# stm32hw05.net
KiCad netlist of a schematic drawn in EAGLE
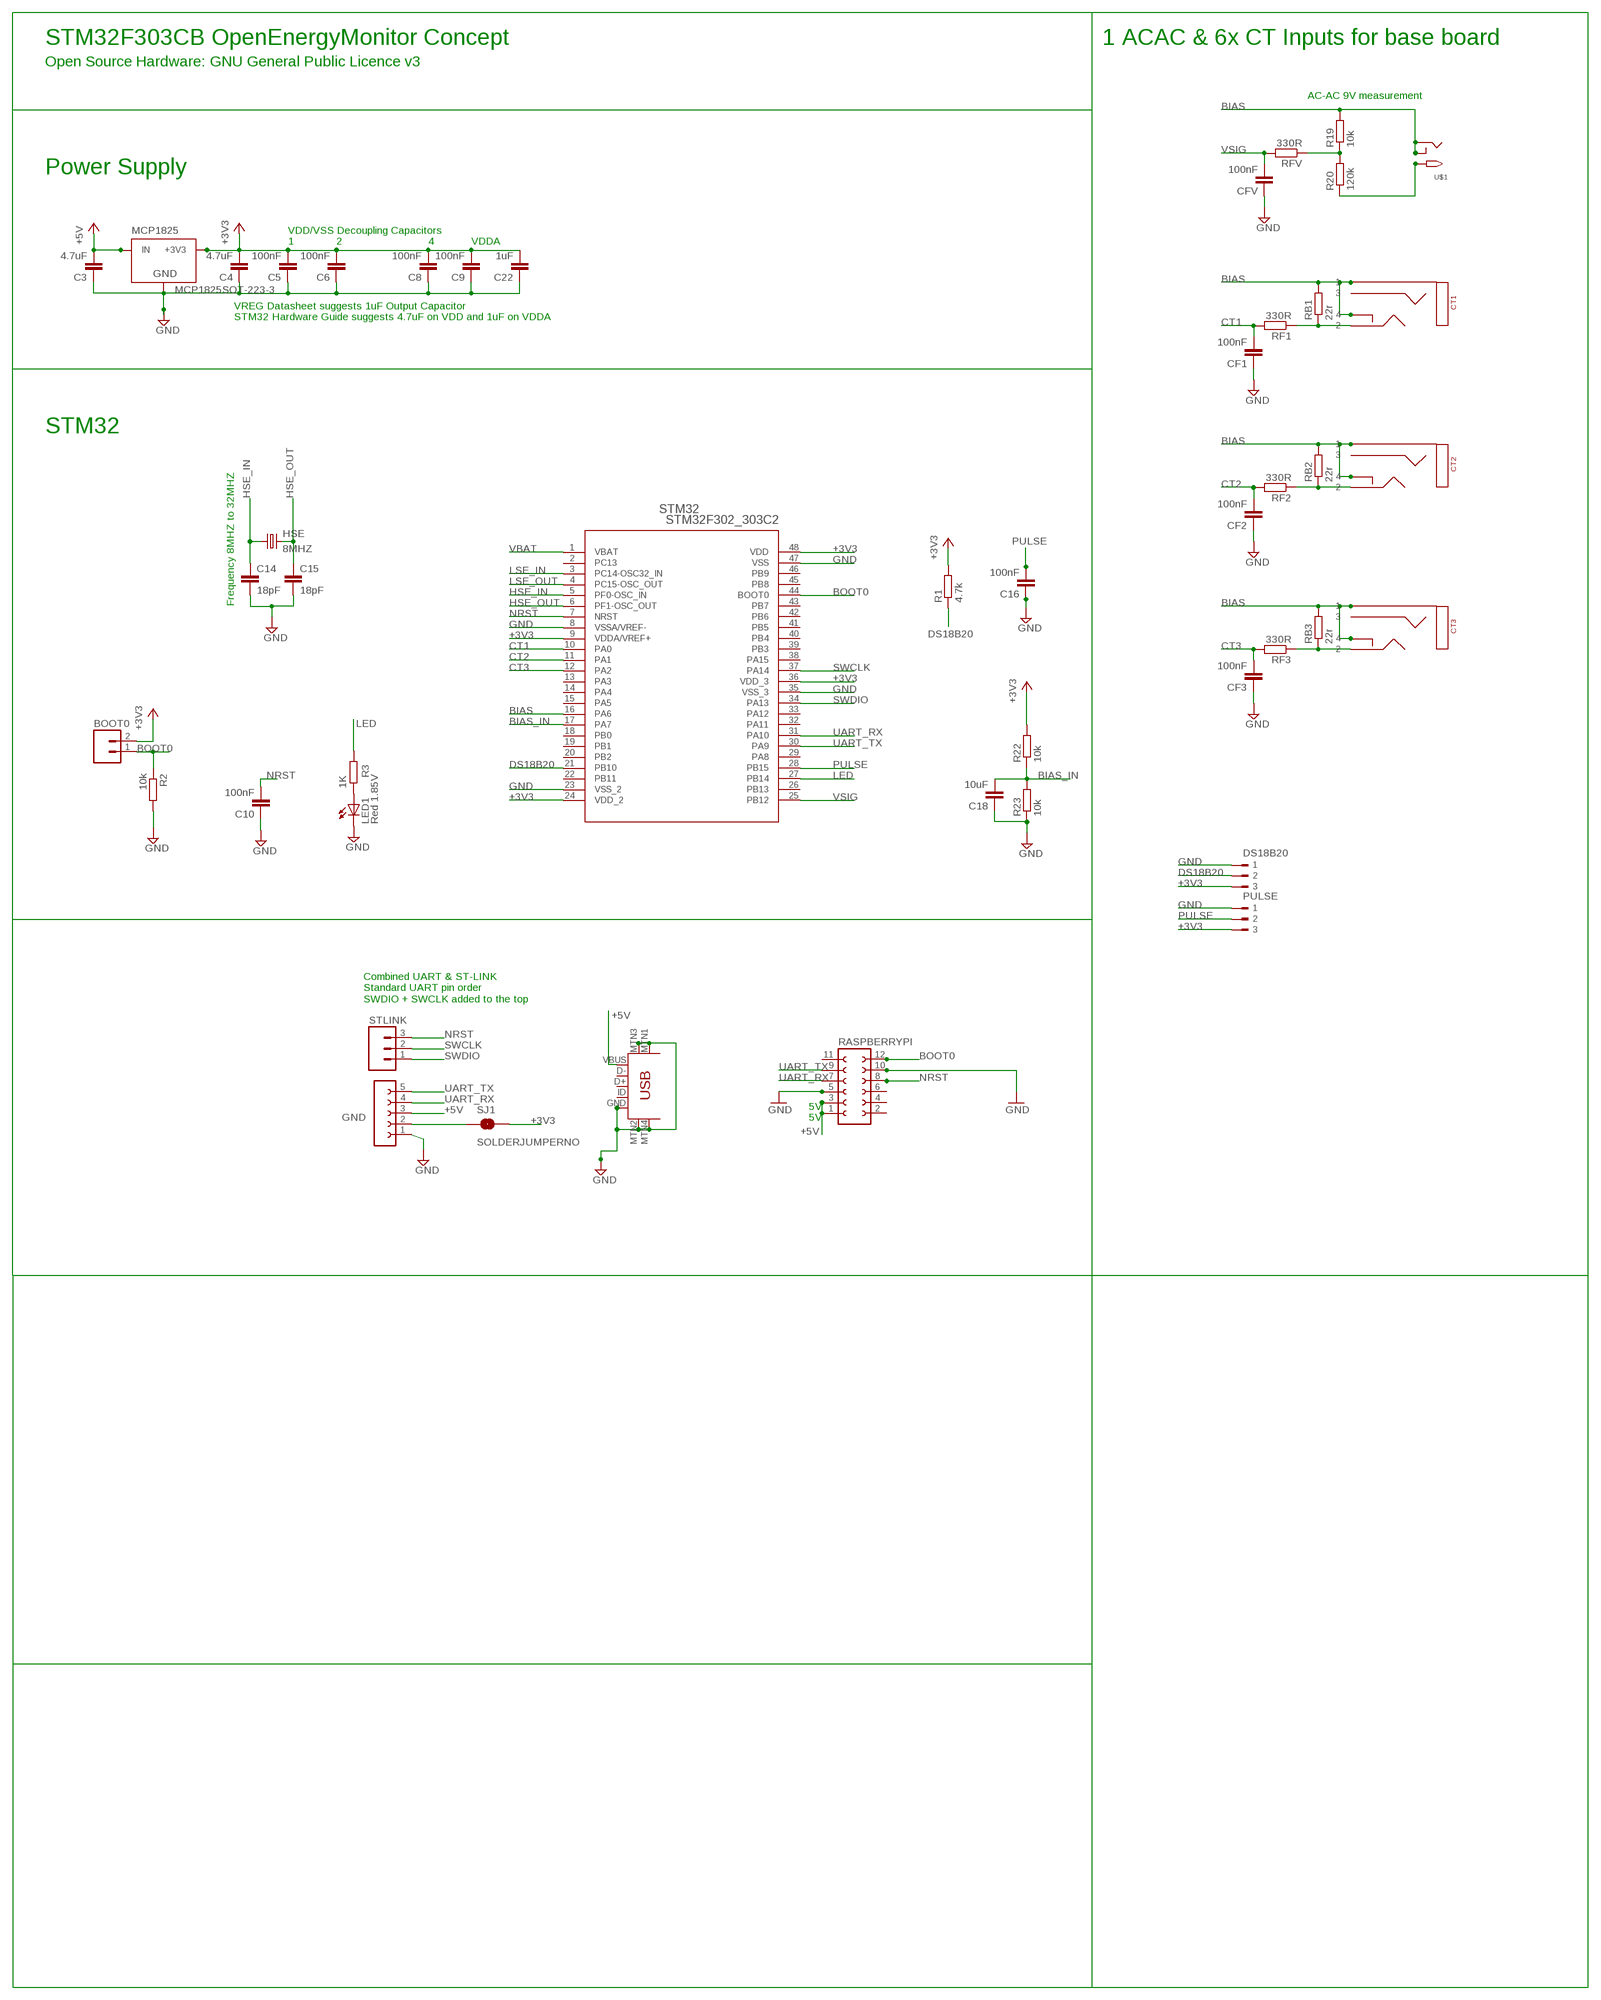
[diagram p0: schematic, sheet 1]

(export (version "E")
  (design (tool "Eeschema 10.0.6"))
  (components
    (comp (ref "BOOT0")
      (value "M02PTH")
      (footprint "eagle-import:1X02")
      (libsource (lib "eagle-import") (part "M02PTH"))
    )
    (comp (ref "C3")
      (value "4.7uF")
      (footprint "eagle-import:C0603")
      (libsource (lib "eagle-import") (part "C-EUC0603"))
    )
    (comp (ref "C4")
      (value "4.7uF")
      (footprint "eagle-import:C0603")
      (libsource (lib "eagle-import") (part "C-EUC0603"))
    )
    (comp (ref "C5")
      (value "100nF")
      (footprint "eagle-import:C0603")
      (libsource (lib "eagle-import") (part "C-EUC0603"))
    )
    (comp (ref "C6")
      (value "100nF")
      (footprint "eagle-import:C0603")
      (libsource (lib "eagle-import") (part "C-EUC0603"))
    )
    (comp (ref "C8")
      (value "100nF")
      (footprint "eagle-import:C0603")
      (libsource (lib "eagle-import") (part "C-EUC0603"))
    )
    (comp (ref "C9")
      (value "100nF")
      (footprint "eagle-import:C0603")
      (libsource (lib "eagle-import") (part "C-EUC0603"))
    )
    (comp (ref "C10")
      (value "100nF")
      (footprint "eagle-import:C0603")
      (libsource (lib "eagle-import") (part "C-EUC0603"))
    )
    (comp (ref "C14")
      (value "18pF")
      (footprint "eagle-import:C0603")
      (libsource (lib "eagle-import") (part "C-EUC0603"))
    )
    (comp (ref "C15")
      (value "18pF")
      (footprint "eagle-import:C0603")
      (libsource (lib "eagle-import") (part "C-EUC0603"))
    )
    (comp (ref "C16")
      (value "100nF")
      (footprint "eagle-import:C0603")
      (libsource (lib "eagle-import") (part "C-EUC0603"))
    )
    (comp (ref "C18")
      (value "10uF")
      (footprint "eagle-import:C0603")
      (libsource (lib "eagle-import") (part "C-EUC0603"))
    )
    (comp (ref "C22")
      (value "1uF")
      (footprint "eagle-import:C0603")
      (libsource (lib "eagle-import") (part "C-EUC0603"))
    )
    (comp (ref "CF1")
      (value "100nF")
      (footprint "eagle-import:C0603")
      (libsource (lib "eagle-import") (part "C-EUC0603"))
    )
    (comp (ref "CF2")
      (value "100nF")
      (footprint "eagle-import:C0603")
      (libsource (lib "eagle-import") (part "C-EUC0603"))
    )
    (comp (ref "CF3")
      (value "100nF")
      (footprint "eagle-import:C0603")
      (libsource (lib "eagle-import") (part "C-EUC0603"))
    )
    (comp (ref "CFV")
      (value "100nF")
      (footprint "eagle-import:C0603")
      (libsource (lib "eagle-import") (part "C-EUC0603"))
    )
    (comp (ref "CT1")
      (value "STEREO_SMD")
      (footprint "eagle-import:STEREO_SMT")
      (libsource (lib "eagle-import") (part "STEREO_SMD"))
    )
    (comp (ref "CT2")
      (value "STEREO_SMD")
      (footprint "eagle-import:STEREO_SMT")
      (libsource (lib "eagle-import") (part "STEREO_SMD"))
    )
    (comp (ref "CT3")
      (value "STEREO_SMD")
      (footprint "eagle-import:STEREO_SMT")
      (libsource (lib "eagle-import") (part "STEREO_SMD"))
    )
    (comp (ref "DS18B20")
      (value "180-3")
      (footprint "eagle-import:180-3")
      (libsource (lib "eagle-import") (part "180-3"))
    )
    (comp (ref "GND")
      (value "UART")
      (footprint "eagle-import:FE05-1")
      (libsource (lib "eagle-import") (part "FE05-1"))
    )
    (comp (ref "HSE")
      (value "8MHZ")
      (footprint "eagle-import:CTS406")
      (libsource (lib "eagle-import") (part "CRYSTALCTS406"))
    )
    (comp (ref "LED1")
      (value "Red 1.85V")
      (footprint "eagle-import:CHIP-LED0805")
      (libsource (lib "eagle-import") (part "LEDCHIP-LED0805"))
    )
    (comp (ref "MCP1825")
      (value "MCP1825SOT-223-3")
      (footprint "eagle-import:SOT-223")
      (libsource (lib "eagle-import") (part "MCP1825SOT-223-3"))
    )
    (comp (ref "PULSE")
      (value "180-3")
      (footprint "eagle-import:180-3")
      (libsource (lib "eagle-import") (part "180-3"))
    )
    (comp (ref "R1")
      (value "4.7k")
      (footprint "eagle-import:R0603")
      (libsource (lib "eagle-import") (part "resistor_R-EU_R0603"))
    )
    (comp (ref "R2")
      (value "10k")
      (footprint "eagle-import:R0603")
      (libsource (lib "eagle-import") (part "resistor_R-EU_R0603"))
    )
    (comp (ref "R3")
      (value "1K")
      (footprint "eagle-import:R0603")
      (libsource (lib "eagle-import") (part "R-EU_R0603"))
    )
    (comp (ref "R19")
      (value "10k")
      (footprint "eagle-import:R0603")
      (libsource (lib "eagle-import") (part "resistor_R-EU_R0603"))
    )
    (comp (ref "R20")
      (value "120k")
      (footprint "eagle-import:R0603")
      (libsource (lib "eagle-import") (part "resistor_R-EU_R0603"))
    )
    (comp (ref "R22")
      (value "10k")
      (footprint "eagle-import:R0603")
      (libsource (lib "eagle-import") (part "resistor_R-EU_R0603"))
    )
    (comp (ref "R23")
      (value "10k")
      (footprint "eagle-import:R0603")
      (libsource (lib "eagle-import") (part "resistor_R-EU_R0603"))
    )
    (comp (ref "RASPBERRYPI")
      (value "FE06-2")
      (footprint "eagle-import:FE06-2")
      (libsource (lib "eagle-import") (part "FE06-2"))
    )
    (comp (ref "RB1")
      (value "22r")
      (footprint "eagle-import:R0603")
      (libsource (lib "eagle-import") (part "resistor_R-EU_R0603"))
    )
    (comp (ref "RB2")
      (value "22r")
      (footprint "eagle-import:R0603")
      (libsource (lib "eagle-import") (part "resistor_R-EU_R0603"))
    )
    (comp (ref "RB3")
      (value "22r")
      (footprint "eagle-import:R0603")
      (libsource (lib "eagle-import") (part "resistor_R-EU_R0603"))
    )
    (comp (ref "RF1")
      (value "330R")
      (footprint "eagle-import:R0603")
      (libsource (lib "eagle-import") (part "resistor_R-EU_R0603"))
    )
    (comp (ref "RF2")
      (value "330R")
      (footprint "eagle-import:R0603")
      (libsource (lib "eagle-import") (part "resistor_R-EU_R0603"))
    )
    (comp (ref "RF3")
      (value "330R")
      (footprint "eagle-import:R0603")
      (libsource (lib "eagle-import") (part "resistor_R-EU_R0603"))
    )
    (comp (ref "RFV")
      (value "330R")
      (footprint "eagle-import:R0603")
      (libsource (lib "eagle-import") (part "resistor_R-EU_R0603"))
    )
    (comp (ref "SJ1")
      (value "SOLDERJUMPERNO")
      (footprint "eagle-import:SJ_2S-NO")
      (libsource (lib "eagle-import") (part "SOLDERJUMPERNO"))
    )
    (comp (ref "STLINK")
      (value "M03PTH")
      (footprint "eagle-import:1X03")
      (libsource (lib "eagle-import") (part "M03PTH"))
    )
    (comp (ref "STM32")
      (value "STM32F302_303C2")
      (footprint "eagle-import:LQFP48-7X7MM")
      (fields (field (name "MANUFACTURER_PART_NUMBER") "stm32f302_303c2"))
      (libsource (lib "eagle-import") (part "STM32F302_303C2"))
    )
    (comp (ref "U$1")
      (value "2.1MMJACKSMT")
      (footprint "eagle-import:DCJACK_2MM_SMT")
      (libsource (lib "eagle-import") (part "2.1MMJACKSMT"))
    )
    (comp (ref "U$10")
      (value "USB-MINIB-5PIN")
      (footprint "eagle-import:USB-MINIB-CISECO")
      (libsource (lib "eagle-import") (part "USB-MINIB-5PIN"))
    )
  )
  (nets
    (net (code "1") (name "+3V3") (class "Default")
      (node (ref "BOOT0") (pin "2") (pinfunction "2_2") (pintype "passive"))
      (node (ref "C22") (pin "2") (pinfunction "2_2") (pintype "passive"))
      (node (ref "C4") (pin "2") (pinfunction "2_2") (pintype "passive"))
      (node (ref "C5") (pin "2") (pinfunction "2_2") (pintype "passive"))
      (node (ref "C6") (pin "2") (pinfunction "2_2") (pintype "passive"))
      (node (ref "C8") (pin "2") (pinfunction "2_2") (pintype "passive"))
      (node (ref "C9") (pin "2") (pinfunction "2_2") (pintype "passive"))
      (node (ref "DS18B20") (pin "3") (pinfunction "3_3") (pintype "passive"))
      (node (ref "MCP1825") (pin "3") (pinfunction "+3V3_3") (pintype "power_in"))
      (node (ref "PULSE") (pin "3") (pinfunction "3_3") (pintype "passive"))
      (node (ref "R1") (pin "2") (pinfunction "2_2") (pintype "passive"))
      (node (ref "R22") (pin "2") (pinfunction "2_2") (pintype "passive"))
      (node (ref "SJ1") (pin "2") (pinfunction "2_2") (pintype "passive"))
      (node (ref "STM32") (pin "24") (pinfunction "VDD_2_24") (pintype "power_in"))
      (node (ref "STM32") (pin "36") (pinfunction "VDD_3_36") (pintype "power_in"))
      (node (ref "STM32") (pin "48") (pinfunction "VDD_48") (pintype "power_in"))
      (node (ref "STM32") (pin "9") (pinfunction "VDDA/VREF+_9") (pintype "power_in"))
    )
    (net (code "2") (name "+5V") (class "Default")
      (node (ref "C3") (pin "2") (pinfunction "2_2") (pintype "passive"))
      (node (ref "GND") (pin "3") (pinfunction "3_3") (pintype "passive"))
      (node (ref "MCP1825") (pin "1") (pinfunction "IN_1") (pintype "power_in"))
      (node (ref "RASPBERRYPI") (pin "1") (pinfunction "1_1") (pintype "passive"))
      (node (ref "RASPBERRYPI") (pin "3") (pinfunction "3_3") (pintype "passive"))
      (node (ref "U$10") (pin "VBUS") (pinfunction "VBUS_VBUS") (pintype "bidirectional"))
    )
    (net (code "3") (name "/BIAS") (class "Default")
      (node (ref "CT1") (pin "P$1") (pinfunction "1_P$1") (pintype "bidirectional"))
      (node (ref "CT1") (pin "P$4") (pinfunction "4_P$4") (pintype "bidirectional"))
      (node (ref "CT2") (pin "P$1") (pinfunction "1_P$1") (pintype "bidirectional"))
      (node (ref "CT2") (pin "P$4") (pinfunction "4_P$4") (pintype "bidirectional"))
      (node (ref "CT3") (pin "P$1") (pinfunction "1_P$1") (pintype "bidirectional"))
      (node (ref "CT3") (pin "P$4") (pinfunction "4_P$4") (pintype "bidirectional"))
      (node (ref "R19") (pin "2") (pinfunction "2_2") (pintype "passive"))
      (node (ref "RB1") (pin "2") (pinfunction "2_2") (pintype "passive"))
      (node (ref "RB2") (pin "2") (pinfunction "2_2") (pintype "passive"))
      (node (ref "RB3") (pin "2") (pinfunction "2_2") (pintype "passive"))
      (node (ref "STM32") (pin "16") (pinfunction "PA6_16") (pintype "bidirectional"))
      (node (ref "U$1") (pin "GND") (pinfunction "RING_GND") (pintype "bidirectional"))
      (node (ref "U$1") (pin "GNDBREAK") (pinfunction "RING_SW_GNDBREAK") (pintype "bidirectional"))
    )
    (net (code "4") (name "/BIAS_IN") (class "Default")
      (node (ref "C18") (pin "2") (pinfunction "2_2") (pintype "passive"))
      (node (ref "R22") (pin "1") (pinfunction "1_1") (pintype "passive"))
      (node (ref "R23") (pin "2") (pinfunction "2_2") (pintype "passive"))
      (node (ref "STM32") (pin "17") (pinfunction "PA7_17") (pintype "bidirectional"))
    )
    (net (code "5") (name "/BOOT0") (class "Default")
      (node (ref "BOOT0") (pin "1") (pinfunction "1_1") (pintype "passive"))
      (node (ref "R2") (pin "1") (pinfunction "1_1") (pintype "passive"))
      (node (ref "RASPBERRYPI") (pin "12") (pinfunction "12_12") (pintype "passive"))
      (node (ref "STM32") (pin "44") (pinfunction "BOOT0_44") (pintype "input"))
    )
    (net (code "6") (name "/CT1") (class "Default")
      (node (ref "CF1") (pin "2") (pinfunction "2_2") (pintype "passive"))
      (node (ref "RF1") (pin "2") (pinfunction "2_2") (pintype "passive"))
      (node (ref "STM32") (pin "10") (pinfunction "PA0_10") (pintype "bidirectional"))
    )
    (net (code "7") (name "/CT2") (class "Default")
      (node (ref "CF2") (pin "2") (pinfunction "2_2") (pintype "passive"))
      (node (ref "RF2") (pin "2") (pinfunction "2_2") (pintype "passive"))
      (node (ref "STM32") (pin "11") (pinfunction "PA1_11") (pintype "bidirectional"))
    )
    (net (code "8") (name "/CT3") (class "Default")
      (node (ref "CF3") (pin "2") (pinfunction "2_2") (pintype "passive"))
      (node (ref "RF3") (pin "2") (pinfunction "2_2") (pintype "passive"))
      (node (ref "STM32") (pin "12") (pinfunction "PA2_12") (pintype "bidirectional"))
    )
    (net (code "9") (name "/DS18B20") (class "Default")
      (node (ref "DS18B20") (pin "2") (pinfunction "2_2") (pintype "passive"))
      (node (ref "R1") (pin "1") (pinfunction "1_1") (pintype "passive"))
      (node (ref "STM32") (pin "21") (pinfunction "PB10_21") (pintype "bidirectional"))
    )
    (net (code "10") (name "/HSE_IN") (class "Default")
      (node (ref "C14") (pin "1") (pinfunction "1_1") (pintype "passive"))
      (node (ref "HSE") (pin "1") (pinfunction "1_1") (pintype "passive"))
      (node (ref "STM32") (pin "5") (pinfunction "PF0-OSC_IN_5") (pintype "bidirectional"))
    )
    (net (code "11") (name "/HSE_OUT") (class "Default")
      (node (ref "C15") (pin "1") (pinfunction "1_1") (pintype "passive"))
      (node (ref "HSE") (pin "3") (pinfunction "2_3") (pintype "passive"))
      (node (ref "STM32") (pin "6") (pinfunction "PF1-OSC_OUT_6") (pintype "bidirectional"))
    )
    (net (code "12") (name "/LED") (class "Default")
      (node (ref "R3") (pin "2") (pinfunction "2_2") (pintype "passive"))
      (node (ref "STM32") (pin "27") (pinfunction "PB14_27") (pintype "bidirectional"))
    )
    (net (code "13") (name "/LSE_IN") (class "Default")
      (node (ref "STM32") (pin "3") (pinfunction "PC14-OSC32_IN_3") (pintype "bidirectional"))
    )
    (net (code "14") (name "/LSE_OUT") (class "Default")
      (node (ref "STM32") (pin "4") (pinfunction "PC15-OSC_OUT_4") (pintype "bidirectional"))
    )
    (net (code "15") (name "/NRST") (class "Default")
      (node (ref "C10") (pin "2") (pinfunction "2_2") (pintype "passive"))
      (node (ref "RASPBERRYPI") (pin "8") (pinfunction "8_8") (pintype "passive"))
      (node (ref "STLINK") (pin "3") (pinfunction "3_3") (pintype "passive"))
      (node (ref "STM32") (pin "7") (pinfunction "NRST_7") (pintype "bidirectional"))
    )
    (net (code "16") (name "/PULSE") (class "Default")
      (node (ref "C16") (pin "2") (pinfunction "2_2") (pintype "passive"))
      (node (ref "PULSE") (pin "2") (pinfunction "2_2") (pintype "passive"))
      (node (ref "STM32") (pin "28") (pinfunction "PB15_28") (pintype "bidirectional"))
    )
    (net (code "17") (name "/SWCLK") (class "Default")
      (node (ref "STLINK") (pin "2") (pinfunction "2_2") (pintype "passive"))
      (node (ref "STM32") (pin "37") (pinfunction "PA14_37") (pintype "bidirectional"))
    )
    (net (code "18") (name "/SWDIO") (class "Default")
      (node (ref "STLINK") (pin "1") (pinfunction "1_1") (pintype "passive"))
      (node (ref "STM32") (pin "34") (pinfunction "PA13_34") (pintype "bidirectional"))
    )
    (net (code "19") (name "/UART_RX") (class "Default")
      (node (ref "GND") (pin "4") (pinfunction "4_4") (pintype "passive"))
      (node (ref "RASPBERRYPI") (pin "7") (pinfunction "7_7") (pintype "passive"))
      (node (ref "STM32") (pin "31") (pinfunction "PA10_31") (pintype "bidirectional"))
    )
    (net (code "20") (name "/UART_TX") (class "Default")
      (node (ref "GND") (pin "5") (pinfunction "5_5") (pintype "passive"))
      (node (ref "RASPBERRYPI") (pin "9") (pinfunction "9_9") (pintype "passive"))
      (node (ref "STM32") (pin "30") (pinfunction "PA9_30") (pintype "bidirectional"))
    )
    (net (code "21") (name "/VBAT") (class "Default")
      (node (ref "STM32") (pin "1") (pinfunction "VBAT_1") (pintype "power_in"))
    )
    (net (code "22") (name "/VSIG") (class "Default")
      (node (ref "CFV") (pin "2") (pinfunction "2_2") (pintype "passive"))
      (node (ref "RFV") (pin "2") (pinfunction "2_2") (pintype "passive"))
      (node (ref "STM32") (pin "25") (pinfunction "PB12_25") (pintype "bidirectional"))
    )
    (net (code "23") (name "GND") (class "Default")
      (node (ref "C10") (pin "1") (pinfunction "1_1") (pintype "passive"))
      (node (ref "C14") (pin "2") (pinfunction "2_2") (pintype "passive"))
      (node (ref "C15") (pin "2") (pinfunction "2_2") (pintype "passive"))
      (node (ref "C16") (pin "1") (pinfunction "1_1") (pintype "passive"))
      (node (ref "C18") (pin "1") (pinfunction "1_1") (pintype "passive"))
      (node (ref "C22") (pin "1") (pinfunction "1_1") (pintype "passive"))
      (node (ref "C3") (pin "1") (pinfunction "1_1") (pintype "passive"))
      (node (ref "C4") (pin "1") (pinfunction "1_1") (pintype "passive"))
      (node (ref "C5") (pin "1") (pinfunction "1_1") (pintype "passive"))
      (node (ref "C6") (pin "1") (pinfunction "1_1") (pintype "passive"))
      (node (ref "C8") (pin "1") (pinfunction "1_1") (pintype "passive"))
      (node (ref "C9") (pin "1") (pinfunction "1_1") (pintype "passive"))
      (node (ref "CF1") (pin "1") (pinfunction "1_1") (pintype "passive"))
      (node (ref "CF2") (pin "1") (pinfunction "1_1") (pintype "passive"))
      (node (ref "CF3") (pin "1") (pinfunction "1_1") (pintype "passive"))
      (node (ref "CFV") (pin "1") (pinfunction "1_1") (pintype "passive"))
      (node (ref "DS18B20") (pin "1") (pinfunction "1_1") (pintype "passive"))
      (node (ref "GND") (pin "1") (pinfunction "1_1") (pintype "passive"))
      (node (ref "LED1") (pin "C") (pinfunction "C_C") (pintype "passive"))
      (node (ref "MCP1825") (pin "2") (pinfunction "GND_2") (pintype "power_in"))
      (node (ref "PULSE") (pin "1") (pinfunction "1_1") (pintype "passive"))
      (node (ref "R2") (pin "2") (pinfunction "2_2") (pintype "passive"))
      (node (ref "R23") (pin "1") (pinfunction "1_1") (pintype "passive"))
      (node (ref "RASPBERRYPI") (pin "10") (pinfunction "10_10") (pintype "passive"))
      (node (ref "RASPBERRYPI") (pin "5") (pinfunction "5_5") (pintype "passive"))
      (node (ref "STM32") (pin "23") (pinfunction "VSS_2_23") (pintype "power_in"))
      (node (ref "STM32") (pin "35") (pinfunction "VSS_3_35") (pintype "power_in"))
      (node (ref "STM32") (pin "47") (pinfunction "VSS_47") (pintype "power_in"))
      (node (ref "STM32") (pin "8") (pinfunction "VSSA/VREF-_8") (pintype "power_in"))
      (node (ref "U$10") (pin "GND") (pinfunction "GND_GND") (pintype "bidirectional"))
      (node (ref "U$10") (pin "MTN1") (pinfunction "MTN2_MTN1") (pintype "bidirectional"))
      (node (ref "U$10") (pin "MTN2") (pinfunction "MTN3_MTN2") (pintype "bidirectional"))
      (node (ref "U$10") (pin "MTN3") (pinfunction "MTN1_MTN3") (pintype "bidirectional"))
      (node (ref "U$10") (pin "MTN4") (pinfunction "MTN4_MTN4") (pintype "bidirectional"))
    )
    (net (code "24") (name "Net-(CT1-2)") (class "Default")
      (node (ref "CT1") (pin "P$2") (pinfunction "2_P$2") (pintype "bidirectional"))
      (node (ref "RB1") (pin "1") (pinfunction "1_1") (pintype "passive"))
      (node (ref "RF1") (pin "1") (pinfunction "1_1") (pintype "passive"))
    )
    (net (code "25") (name "Net-(CT2-2)") (class "Default")
      (node (ref "CT2") (pin "P$2") (pinfunction "2_P$2") (pintype "bidirectional"))
      (node (ref "RB2") (pin "1") (pinfunction "1_1") (pintype "passive"))
      (node (ref "RF2") (pin "1") (pinfunction "1_1") (pintype "passive"))
    )
    (net (code "26") (name "Net-(CT3-2)") (class "Default")
      (node (ref "CT3") (pin "P$2") (pinfunction "2_P$2") (pintype "bidirectional"))
      (node (ref "RB3") (pin "1") (pinfunction "1_1") (pintype "passive"))
      (node (ref "RF3") (pin "1") (pinfunction "1_1") (pintype "passive"))
    )
    (net (code "27") (name "Net-(GND-Pad2)") (class "Default")
      (node (ref "GND") (pin "2") (pinfunction "2_2") (pintype "passive"))
      (node (ref "SJ1") (pin "1") (pinfunction "1_1") (pintype "passive"))
    )
    (net (code "28") (name "Net-(LED1-PadA)") (class "Default")
      (node (ref "LED1") (pin "A") (pinfunction "A_A") (pintype "passive"))
      (node (ref "R3") (pin "1") (pinfunction "1_1") (pintype "passive"))
    )
    (net (code "29") (name "Net-(R19-Pad1)") (class "Default")
      (node (ref "R19") (pin "1") (pinfunction "1_1") (pintype "passive"))
      (node (ref "R20") (pin "2") (pinfunction "2_2") (pintype "passive"))
      (node (ref "RFV") (pin "1") (pinfunction "1_1") (pintype "passive"))
    )
    (net (code "30") (name "Net-(U$1-TIP)") (class "Default")
      (node (ref "R20") (pin "1") (pinfunction "1_1") (pintype "passive"))
      (node (ref "U$1") (pin "PWR2") (pinfunction "TIP_PWR2") (pintype "bidirectional"))
    )
    (net (code "31") (name "unconnected-(CT1-3-PadP$3)") (class "Default")
      (node (ref "CT1") (pin "P$3") (pinfunction "3_P$3") (pintype "bidirectional"))
    )
    (net (code "32") (name "unconnected-(CT2-3-PadP$3)") (class "Default")
      (node (ref "CT2") (pin "P$3") (pinfunction "3_P$3") (pintype "bidirectional"))
    )
    (net (code "33") (name "unconnected-(CT3-3-PadP$3)") (class "Default")
      (node (ref "CT3") (pin "P$3") (pinfunction "3_P$3") (pintype "bidirectional"))
    )
    (net (code "34") (name "unconnected-(RASPBERRYPI-Pad2)") (class "Default")
      (node (ref "RASPBERRYPI") (pin "2") (pinfunction "2_2") (pintype "passive"))
    )
    (net (code "35") (name "unconnected-(RASPBERRYPI-Pad4)") (class "Default")
      (node (ref "RASPBERRYPI") (pin "4") (pinfunction "4_4") (pintype "passive"))
    )
    (net (code "36") (name "unconnected-(RASPBERRYPI-Pad6)") (class "Default")
      (node (ref "RASPBERRYPI") (pin "6") (pinfunction "6_6") (pintype "passive"))
    )
    (net (code "37") (name "unconnected-(RASPBERRYPI-Pad11)") (class "Default")
      (node (ref "RASPBERRYPI") (pin "11") (pinfunction "11_11") (pintype "passive"))
    )
    (net (code "38") (name "unconnected-(STM32-PA3-Pad13)") (class "Default")
      (node (ref "STM32") (pin "13") (pinfunction "PA3_13") (pintype "bidirectional"))
    )
    (net (code "39") (name "unconnected-(STM32-PA4-Pad14)") (class "Default")
      (node (ref "STM32") (pin "14") (pinfunction "PA4_14") (pintype "bidirectional"))
    )
    (net (code "40") (name "unconnected-(STM32-PA5-Pad15)") (class "Default")
      (node (ref "STM32") (pin "15") (pinfunction "PA5_15") (pintype "bidirectional"))
    )
    (net (code "41") (name "unconnected-(STM32-PA8-Pad29)") (class "Default")
      (node (ref "STM32") (pin "29") (pinfunction "PA8_29") (pintype "bidirectional"))
    )
    (net (code "42") (name "unconnected-(STM32-PA11-Pad32)") (class "Default")
      (node (ref "STM32") (pin "32") (pinfunction "PA11_32") (pintype "bidirectional"))
    )
    (net (code "43") (name "unconnected-(STM32-PA12-Pad33)") (class "Default")
      (node (ref "STM32") (pin "33") (pinfunction "PA12_33") (pintype "bidirectional"))
    )
    (net (code "44") (name "unconnected-(STM32-PA15-Pad38)") (class "Default")
      (node (ref "STM32") (pin "38") (pinfunction "PA15_38") (pintype "bidirectional"))
    )
    (net (code "45") (name "unconnected-(STM32-PB0-Pad18)") (class "Default")
      (node (ref "STM32") (pin "18") (pinfunction "PB0_18") (pintype "bidirectional"))
    )
    (net (code "46") (name "unconnected-(STM32-PB1-Pad19)") (class "Default")
      (node (ref "STM32") (pin "19") (pinfunction "PB1_19") (pintype "bidirectional"))
    )
    (net (code "47") (name "unconnected-(STM32-PB2-Pad20)") (class "Default")
      (node (ref "STM32") (pin "20") (pinfunction "PB2_20") (pintype "bidirectional"))
    )
    (net (code "48") (name "unconnected-(STM32-PB3-Pad39)") (class "Default")
      (node (ref "STM32") (pin "39") (pinfunction "PB3_39") (pintype "bidirectional"))
    )
    (net (code "49") (name "unconnected-(STM32-PB4-Pad40)") (class "Default")
      (node (ref "STM32") (pin "40") (pinfunction "PB4_40") (pintype "bidirectional"))
    )
    (net (code "50") (name "unconnected-(STM32-PB5-Pad41)") (class "Default")
      (node (ref "STM32") (pin "41") (pinfunction "PB5_41") (pintype "bidirectional"))
    )
    (net (code "51") (name "unconnected-(STM32-PB6-Pad42)") (class "Default")
      (node (ref "STM32") (pin "42") (pinfunction "PB6_42") (pintype "bidirectional"))
    )
    (net (code "52") (name "unconnected-(STM32-PB7-Pad43)") (class "Default")
      (node (ref "STM32") (pin "43") (pinfunction "PB7_43") (pintype "bidirectional"))
    )
    (net (code "53") (name "unconnected-(STM32-PB8-Pad45)") (class "Default")
      (node (ref "STM32") (pin "45") (pinfunction "PB8_45") (pintype "bidirectional"))
    )
    (net (code "54") (name "unconnected-(STM32-PB9-Pad46)") (class "Default")
      (node (ref "STM32") (pin "46") (pinfunction "PB9_46") (pintype "bidirectional"))
    )
    (net (code "55") (name "unconnected-(STM32-PB11-Pad22)") (class "Default")
      (node (ref "STM32") (pin "22") (pinfunction "PB11_22") (pintype "bidirectional"))
    )
    (net (code "56") (name "unconnected-(STM32-PB13-Pad26)") (class "Default")
      (node (ref "STM32") (pin "26") (pinfunction "PB13_26") (pintype "bidirectional"))
    )
    (net (code "57") (name "unconnected-(STM32-PC13-Pad2)") (class "Default")
      (node (ref "STM32") (pin "2") (pinfunction "PC13_2") (pintype "bidirectional"))
    )
    (net (code "58") (name "unconnected-(U$10-PadD+)") (class "Default")
      (node (ref "U$10") (pin "D+") (pinfunction "D+_D+") (pintype "bidirectional"))
    )
    (net (code "59") (name "unconnected-(U$10-PadD-)") (class "Default")
      (node (ref "U$10") (pin "D-") (pinfunction "D-_D-") (pintype "bidirectional"))
    )
    (net (code "60") (name "unconnected-(U$10-PadID)") (class "Default")
      (node (ref "U$10") (pin "ID") (pinfunction "ID_ID") (pintype "bidirectional"))
    )
  )
)
